# A7_MGT.net
KiCad netlist of a schematic drawn in Altium Designer
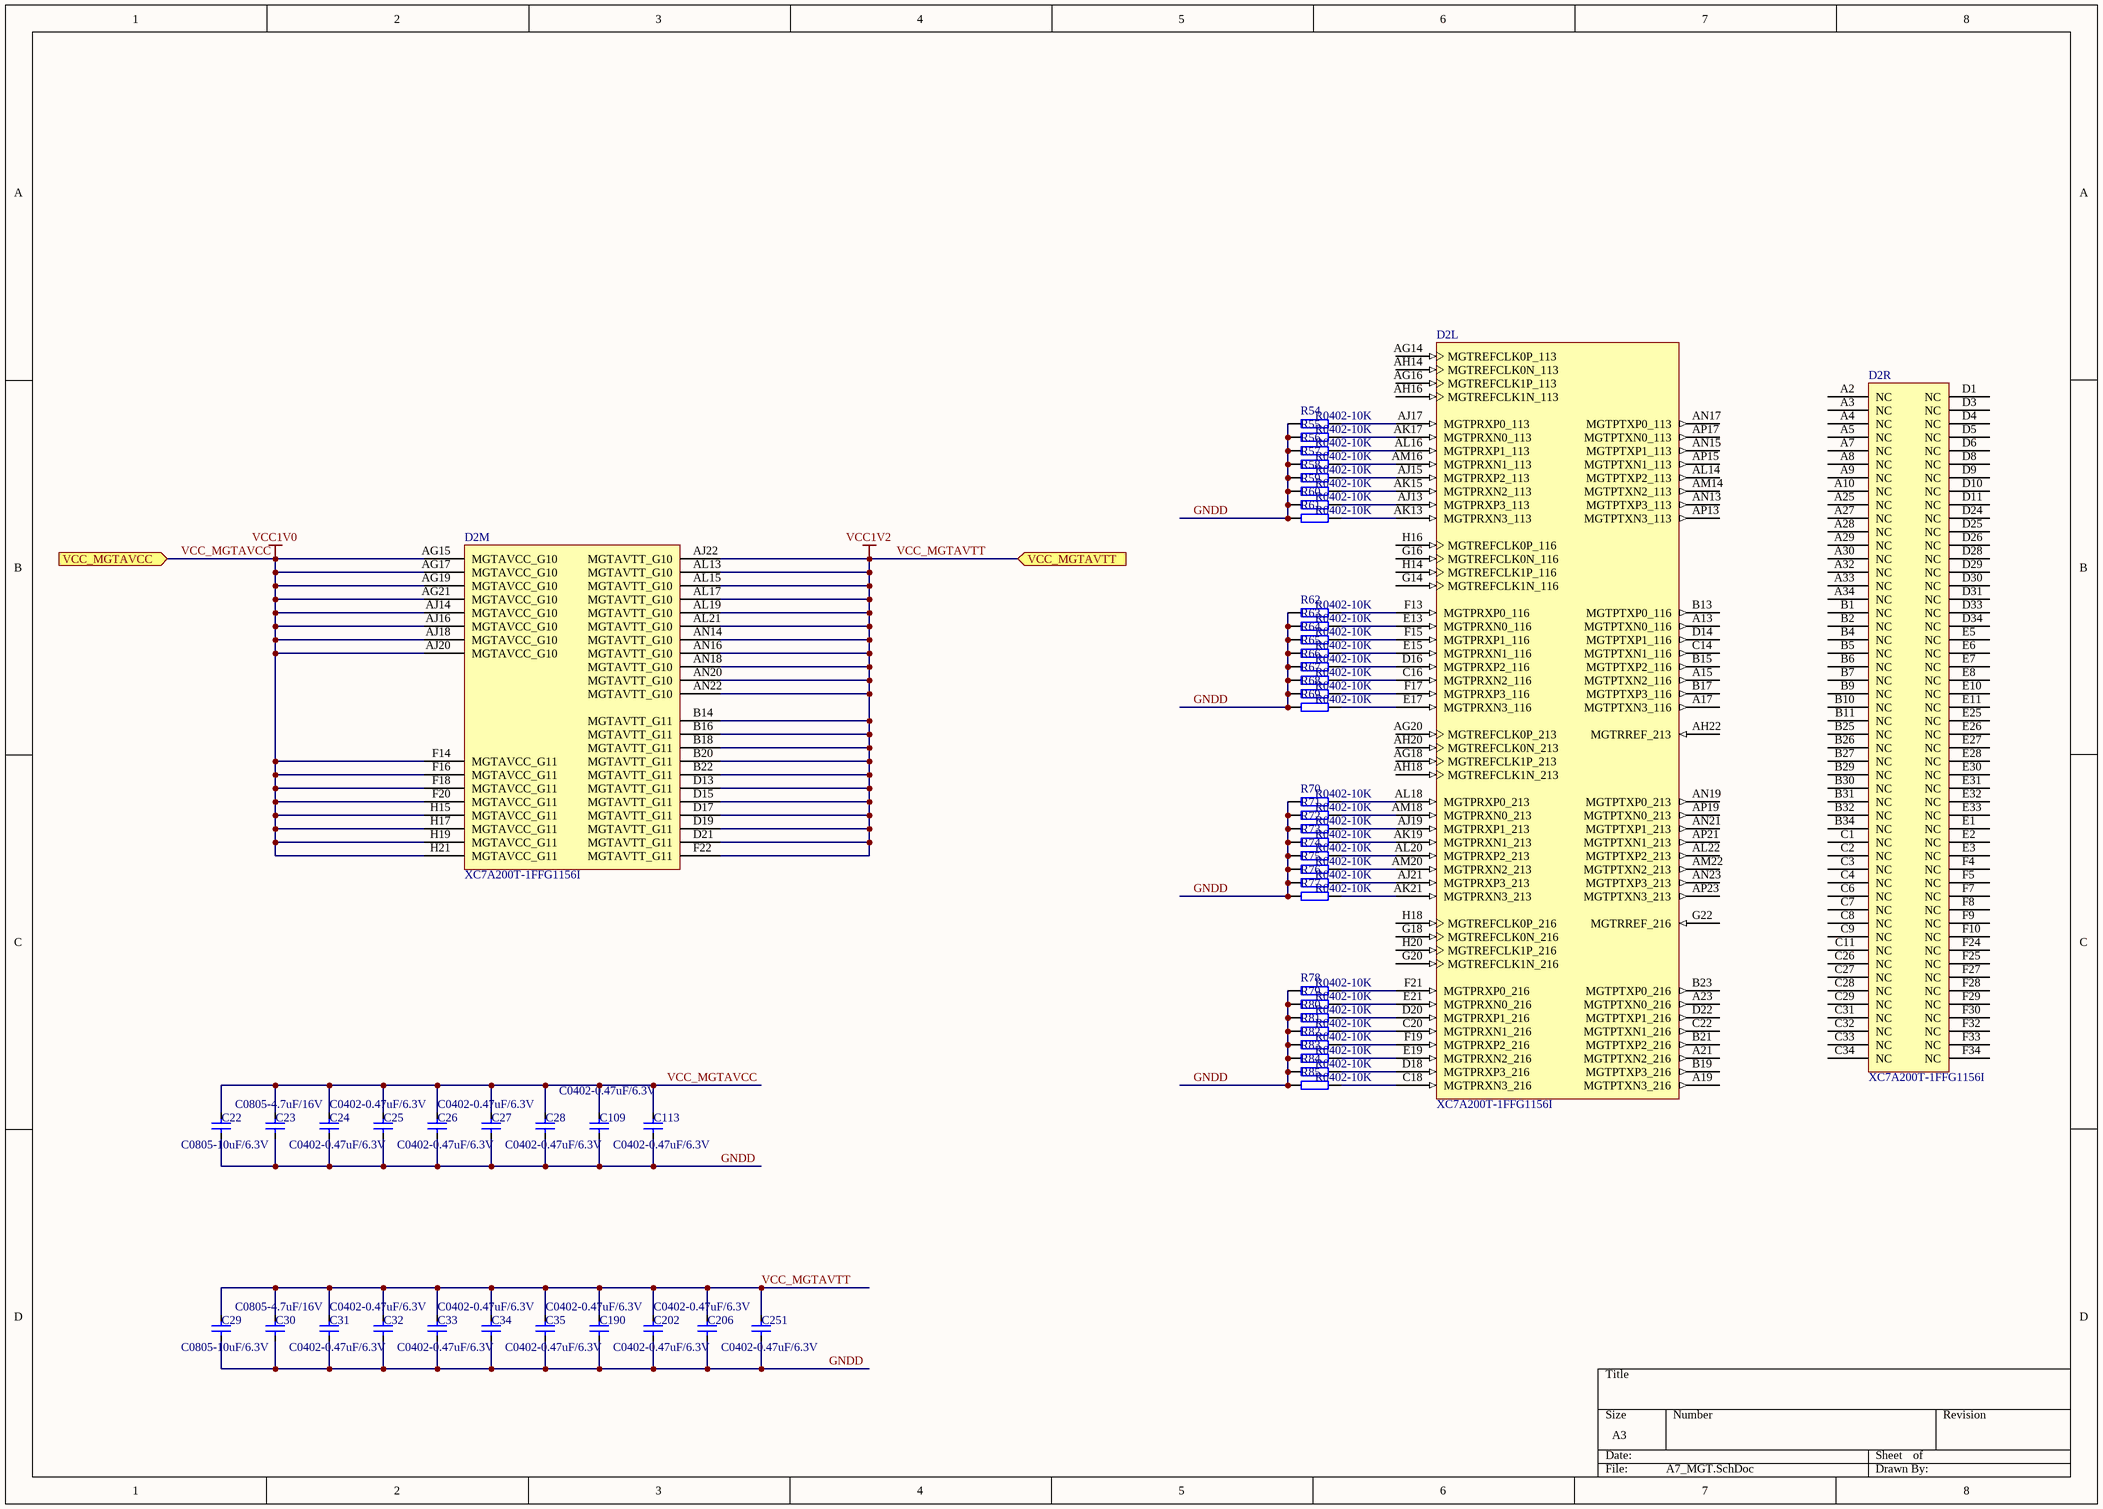
[diagram p0: A7_MGT.SchDoc]

(export (version "E")
  (design (tool "Eeschema 10.0.6"))
  (components
    (comp (ref "C22")
      (value "C0805-10uF/6.3V")
      (footprint "C0805")
      (fields (field (name "SCHEMATIC_PART") "CAP"))
      (libsource (lib "Database_Libs1") (part "CAP"))
    )
    (comp (ref "C23")
      (value "C0805-4.7uF/16V")
      (footprint "C0805")
      (description "X7R")
      (fields (field (name "SCHEMATIC_PART") "CAP") (field (name "MANUFACTURER") "SAMSUNG"))
      (libsource (lib "Database_Libs1") (part "CAP"))
    )
    (comp (ref "C24")
      (value "C0402-0.47uF/6.3V")
      (footprint "C0402")
      (description "X7R")
      (fields (field (name "SCHEMATIC_PART") "CAP") (field (name "MANUFACTURER") "SAMSUNG"))
      (libsource (lib "Database_Libs1") (part "CAP"))
    )
    (comp (ref "C25")
      (value "C0402-0.47uF/6.3V")
      (footprint "C0402")
      (description "X7R")
      (fields (field (name "SCHEMATIC_PART") "CAP") (field (name "MANUFACTURER") "SAMSUNG"))
      (libsource (lib "Database_Libs1") (part "CAP"))
    )
    (comp (ref "C26")
      (value "C0402-0.47uF/6.3V")
      (footprint "C0402")
      (description "X7R")
      (fields (field (name "SCHEMATIC_PART") "CAP") (field (name "MANUFACTURER") "SAMSUNG"))
      (libsource (lib "Database_Libs1") (part "CAP"))
    )
    (comp (ref "C27")
      (value "C0402-0.47uF/6.3V")
      (footprint "C0402")
      (description "X7R")
      (fields (field (name "SCHEMATIC_PART") "CAP") (field (name "MANUFACTURER") "SAMSUNG"))
      (libsource (lib "Database_Libs1") (part "CAP"))
    )
    (comp (ref "C28")
      (value "C0402-0.47uF/6.3V")
      (footprint "C0402")
      (description "X7R")
      (fields (field (name "SCHEMATIC_PART") "CAP") (field (name "MANUFACTURER") "SAMSUNG"))
      (libsource (lib "Database_Libs1") (part "CAP"))
    )
    (comp (ref "C29")
      (value "C0805-10uF/6.3V")
      (footprint "C0805")
      (fields (field (name "SCHEMATIC_PART") "CAP"))
      (libsource (lib "Database_Libs1") (part "CAP"))
    )
    (comp (ref "C30")
      (value "C0805-4.7uF/16V")
      (footprint "C0805")
      (description "X7R")
      (fields (field (name "SCHEMATIC_PART") "CAP") (field (name "MANUFACTURER") "SAMSUNG"))
      (libsource (lib "Database_Libs1") (part "CAP"))
    )
    (comp (ref "C31")
      (value "C0402-0.47uF/6.3V")
      (footprint "C0402")
      (description "X7R")
      (fields (field (name "SCHEMATIC_PART") "CAP") (field (name "MANUFACTURER") "SAMSUNG"))
      (libsource (lib "Database_Libs1") (part "CAP"))
    )
    (comp (ref "C32")
      (value "C0402-0.47uF/6.3V")
      (footprint "C0402")
      (description "X7R")
      (fields (field (name "SCHEMATIC_PART") "CAP") (field (name "MANUFACTURER") "SAMSUNG"))
      (libsource (lib "Database_Libs1") (part "CAP"))
    )
    (comp (ref "C33")
      (value "C0402-0.47uF/6.3V")
      (footprint "C0402")
      (description "X7R")
      (fields (field (name "SCHEMATIC_PART") "CAP") (field (name "MANUFACTURER") "SAMSUNG"))
      (libsource (lib "Database_Libs1") (part "CAP"))
    )
    (comp (ref "C34")
      (value "C0402-0.47uF/6.3V")
      (footprint "C0402")
      (description "X7R")
      (fields (field (name "SCHEMATIC_PART") "CAP") (field (name "MANUFACTURER") "SAMSUNG"))
      (libsource (lib "Database_Libs1") (part "CAP"))
    )
    (comp (ref "C35")
      (value "C0402-0.47uF/6.3V")
      (footprint "C0402")
      (description "X7R")
      (fields (field (name "SCHEMATIC_PART") "CAP") (field (name "MANUFACTURER") "SAMSUNG"))
      (libsource (lib "Database_Libs1") (part "CAP"))
    )
    (comp (ref "C109")
      (value "C0402-0.47uF/6.3V")
      (footprint "C0402")
      (description "X7R")
      (fields (field (name "SCHEMATIC_PART") "CAP") (field (name "MANUFACTURER") "SAMSUNG"))
      (libsource (lib "Database_Libs1") (part "CAP"))
    )
    (comp (ref "C113")
      (value "C0402-0.47uF/6.3V")
      (footprint "C0402")
      (description "X7R")
      (fields (field (name "SCHEMATIC_PART") "CAP") (field (name "MANUFACTURER") "SAMSUNG"))
      (libsource (lib "Database_Libs1") (part "CAP"))
    )
    (comp (ref "C190")
      (value "C0402-0.47uF/6.3V")
      (footprint "C0402")
      (description "X7R")
      (fields (field (name "SCHEMATIC_PART") "CAP") (field (name "MANUFACTURER") "SAMSUNG"))
      (libsource (lib "Database_Libs1") (part "CAP"))
    )
    (comp (ref "C202")
      (value "C0402-0.47uF/6.3V")
      (footprint "C0402")
      (description "X7R")
      (fields (field (name "SCHEMATIC_PART") "CAP") (field (name "MANUFACTURER") "SAMSUNG"))
      (libsource (lib "Database_Libs1") (part "CAP"))
    )
    (comp (ref "C206")
      (value "C0402-0.47uF/6.3V")
      (footprint "C0402")
      (description "X7R")
      (fields (field (name "SCHEMATIC_PART") "CAP") (field (name "MANUFACTURER") "SAMSUNG"))
      (libsource (lib "Database_Libs1") (part "CAP"))
    )
    (comp (ref "C251")
      (value "C0402-0.47uF/6.3V")
      (footprint "C0402")
      (description "X7R")
      (fields (field (name "SCHEMATIC_PART") "CAP") (field (name "MANUFACTURER") "SAMSUNG"))
      (libsource (lib "Database_Libs1") (part "CAP"))
    )
    (comp (ref "D2")
      (value "XC7A200T-1FFG1156I")
      (footprint "FFG1156")
      (description "Artix-7 FPGA, 500 User I/Os, 16 GTP, 1156-Ball BGA, Speed Grade 1, Industrial Grade, Pb-Free")
      (fields (field (name "GENERIC PART NUMBER") "XC7A200T") (field (name "MANUFACTURER") "Xilinx"))
      (libsource (lib "Xilinx Artix-7") (part "XC7A200T-1FFG1156I"))
    )
    (comp (ref "R54")
      (value "R0402-10K")
      (footprint "R0402")
      (fields (field (name "SCHEMATIC_PART") "RES") (field (name "MANUFACTURER") "SAMSUNG"))
      (libsource (lib "Database_Libs1") (part "RES"))
    )
    (comp (ref "R55")
      (value "R0402-10K")
      (footprint "R0402")
      (fields (field (name "SCHEMATIC_PART") "RES") (field (name "MANUFACTURER") "SAMSUNG"))
      (libsource (lib "Database_Libs1") (part "RES"))
    )
    (comp (ref "R56")
      (value "R0402-10K")
      (footprint "R0402")
      (fields (field (name "SCHEMATIC_PART") "RES") (field (name "MANUFACTURER") "SAMSUNG"))
      (libsource (lib "Database_Libs1") (part "RES"))
    )
    (comp (ref "R57")
      (value "R0402-10K")
      (footprint "R0402")
      (fields (field (name "SCHEMATIC_PART") "RES") (field (name "MANUFACTURER") "SAMSUNG"))
      (libsource (lib "Database_Libs1") (part "RES"))
    )
    (comp (ref "R58")
      (value "R0402-10K")
      (footprint "R0402")
      (fields (field (name "SCHEMATIC_PART") "RES") (field (name "MANUFACTURER") "SAMSUNG"))
      (libsource (lib "Database_Libs1") (part "RES"))
    )
    (comp (ref "R59")
      (value "R0402-10K")
      (footprint "R0402")
      (fields (field (name "SCHEMATIC_PART") "RES") (field (name "MANUFACTURER") "SAMSUNG"))
      (libsource (lib "Database_Libs1") (part "RES"))
    )
    (comp (ref "R60")
      (value "R0402-10K")
      (footprint "R0402")
      (fields (field (name "SCHEMATIC_PART") "RES") (field (name "MANUFACTURER") "SAMSUNG"))
      (libsource (lib "Database_Libs1") (part "RES"))
    )
    (comp (ref "R61")
      (value "R0402-10K")
      (footprint "R0402")
      (fields (field (name "SCHEMATIC_PART") "RES") (field (name "MANUFACTURER") "SAMSUNG"))
      (libsource (lib "Database_Libs1") (part "RES"))
    )
    (comp (ref "R62")
      (value "R0402-10K")
      (footprint "R0402")
      (fields (field (name "SCHEMATIC_PART") "RES") (field (name "MANUFACTURER") "SAMSUNG"))
      (libsource (lib "Database_Libs1") (part "RES"))
    )
    (comp (ref "R63")
      (value "R0402-10K")
      (footprint "R0402")
      (fields (field (name "SCHEMATIC_PART") "RES") (field (name "MANUFACTURER") "SAMSUNG"))
      (libsource (lib "Database_Libs1") (part "RES"))
    )
    (comp (ref "R64")
      (value "R0402-10K")
      (footprint "R0402")
      (fields (field (name "SCHEMATIC_PART") "RES") (field (name "MANUFACTURER") "SAMSUNG"))
      (libsource (lib "Database_Libs1") (part "RES"))
    )
    (comp (ref "R65")
      (value "R0402-10K")
      (footprint "R0402")
      (fields (field (name "SCHEMATIC_PART") "RES") (field (name "MANUFACTURER") "SAMSUNG"))
      (libsource (lib "Database_Libs1") (part "RES"))
    )
    (comp (ref "R66")
      (value "R0402-10K")
      (footprint "R0402")
      (fields (field (name "SCHEMATIC_PART") "RES") (field (name "MANUFACTURER") "SAMSUNG"))
      (libsource (lib "Database_Libs1") (part "RES"))
    )
    (comp (ref "R67")
      (value "R0402-10K")
      (footprint "R0402")
      (fields (field (name "SCHEMATIC_PART") "RES") (field (name "MANUFACTURER") "SAMSUNG"))
      (libsource (lib "Database_Libs1") (part "RES"))
    )
    (comp (ref "R68")
      (value "R0402-10K")
      (footprint "R0402")
      (fields (field (name "SCHEMATIC_PART") "RES") (field (name "MANUFACTURER") "SAMSUNG"))
      (libsource (lib "Database_Libs1") (part "RES"))
    )
    (comp (ref "R69")
      (value "R0402-10K")
      (footprint "R0402")
      (fields (field (name "SCHEMATIC_PART") "RES") (field (name "MANUFACTURER") "SAMSUNG"))
      (libsource (lib "Database_Libs1") (part "RES"))
    )
    (comp (ref "R70")
      (value "R0402-10K")
      (footprint "R0402")
      (fields (field (name "SCHEMATIC_PART") "RES") (field (name "MANUFACTURER") "SAMSUNG"))
      (libsource (lib "Database_Libs1") (part "RES"))
    )
    (comp (ref "R71")
      (value "R0402-10K")
      (footprint "R0402")
      (fields (field (name "SCHEMATIC_PART") "RES") (field (name "MANUFACTURER") "SAMSUNG"))
      (libsource (lib "Database_Libs1") (part "RES"))
    )
    (comp (ref "R72")
      (value "R0402-10K")
      (footprint "R0402")
      (fields (field (name "SCHEMATIC_PART") "RES") (field (name "MANUFACTURER") "SAMSUNG"))
      (libsource (lib "Database_Libs1") (part "RES"))
    )
    (comp (ref "R73")
      (value "R0402-10K")
      (footprint "R0402")
      (fields (field (name "SCHEMATIC_PART") "RES") (field (name "MANUFACTURER") "SAMSUNG"))
      (libsource (lib "Database_Libs1") (part "RES"))
    )
    (comp (ref "R74")
      (value "R0402-10K")
      (footprint "R0402")
      (fields (field (name "SCHEMATIC_PART") "RES") (field (name "MANUFACTURER") "SAMSUNG"))
      (libsource (lib "Database_Libs1") (part "RES"))
    )
    (comp (ref "R75")
      (value "R0402-10K")
      (footprint "R0402")
      (fields (field (name "SCHEMATIC_PART") "RES") (field (name "MANUFACTURER") "SAMSUNG"))
      (libsource (lib "Database_Libs1") (part "RES"))
    )
    (comp (ref "R76")
      (value "R0402-10K")
      (footprint "R0402")
      (fields (field (name "SCHEMATIC_PART") "RES") (field (name "MANUFACTURER") "SAMSUNG"))
      (libsource (lib "Database_Libs1") (part "RES"))
    )
    (comp (ref "R77")
      (value "R0402-10K")
      (footprint "R0402")
      (fields (field (name "SCHEMATIC_PART") "RES") (field (name "MANUFACTURER") "SAMSUNG"))
      (libsource (lib "Database_Libs1") (part "RES"))
    )
    (comp (ref "R78")
      (value "R0402-10K")
      (footprint "R0402")
      (fields (field (name "SCHEMATIC_PART") "RES") (field (name "MANUFACTURER") "SAMSUNG"))
      (libsource (lib "Database_Libs1") (part "RES"))
    )
    (comp (ref "R79")
      (value "R0402-10K")
      (footprint "R0402")
      (fields (field (name "SCHEMATIC_PART") "RES") (field (name "MANUFACTURER") "SAMSUNG"))
      (libsource (lib "Database_Libs1") (part "RES"))
    )
    (comp (ref "R80")
      (value "R0402-10K")
      (footprint "R0402")
      (fields (field (name "SCHEMATIC_PART") "RES") (field (name "MANUFACTURER") "SAMSUNG"))
      (libsource (lib "Database_Libs1") (part "RES"))
    )
    (comp (ref "R81")
      (value "R0402-10K")
      (footprint "R0402")
      (fields (field (name "SCHEMATIC_PART") "RES") (field (name "MANUFACTURER") "SAMSUNG"))
      (libsource (lib "Database_Libs1") (part "RES"))
    )
    (comp (ref "R82")
      (value "R0402-10K")
      (footprint "R0402")
      (fields (field (name "SCHEMATIC_PART") "RES") (field (name "MANUFACTURER") "SAMSUNG"))
      (libsource (lib "Database_Libs1") (part "RES"))
    )
    (comp (ref "R83")
      (value "R0402-10K")
      (footprint "R0402")
      (fields (field (name "SCHEMATIC_PART") "RES") (field (name "MANUFACTURER") "SAMSUNG"))
      (libsource (lib "Database_Libs1") (part "RES"))
    )
    (comp (ref "R84")
      (value "R0402-10K")
      (footprint "R0402")
      (fields (field (name "SCHEMATIC_PART") "RES") (field (name "MANUFACTURER") "SAMSUNG"))
      (libsource (lib "Database_Libs1") (part "RES"))
    )
    (comp (ref "R85")
      (value "R0402-10K")
      (footprint "R0402")
      (fields (field (name "SCHEMATIC_PART") "RES") (field (name "MANUFACTURER") "SAMSUNG"))
      (libsource (lib "Database_Libs1") (part "RES"))
    )
  )
  (nets
    (net (code "1") (name "/GNDD") (class "Default")
      (node (ref "C109") (pin "2") (pinfunction "2_2") (pintype "passive"))
      (node (ref "C113") (pin "2") (pinfunction "2_2") (pintype "passive"))
      (node (ref "C190") (pin "2") (pinfunction "2_2") (pintype "passive"))
      (node (ref "C202") (pin "2") (pinfunction "2_2") (pintype "passive"))
      (node (ref "C206") (pin "2") (pinfunction "2_2") (pintype "passive"))
      (node (ref "C22") (pin "2") (pinfunction "2_2") (pintype "passive"))
      (node (ref "C23") (pin "2") (pinfunction "2_2") (pintype "passive"))
      (node (ref "C24") (pin "2") (pinfunction "2_2") (pintype "passive"))
      (node (ref "C25") (pin "2") (pinfunction "2_2") (pintype "passive"))
      (node (ref "C251") (pin "2") (pinfunction "2_2") (pintype "passive"))
      (node (ref "C26") (pin "2") (pinfunction "2_2") (pintype "passive"))
      (node (ref "C27") (pin "2") (pinfunction "2_2") (pintype "passive"))
      (node (ref "C28") (pin "2") (pinfunction "2_2") (pintype "passive"))
      (node (ref "C29") (pin "2") (pinfunction "2_2") (pintype "passive"))
      (node (ref "C30") (pin "2") (pinfunction "2_2") (pintype "passive"))
      (node (ref "C31") (pin "2") (pinfunction "2_2") (pintype "passive"))
      (node (ref "C32") (pin "2") (pinfunction "2_2") (pintype "passive"))
      (node (ref "C33") (pin "2") (pinfunction "2_2") (pintype "passive"))
      (node (ref "C34") (pin "2") (pinfunction "2_2") (pintype "passive"))
      (node (ref "C35") (pin "2") (pinfunction "2_2") (pintype "passive"))
      (node (ref "R54") (pin "1") (pintype "passive"))
      (node (ref "R55") (pin "1") (pintype "passive"))
      (node (ref "R56") (pin "1") (pintype "passive"))
      (node (ref "R57") (pin "1") (pintype "passive"))
      (node (ref "R58") (pin "1") (pintype "passive"))
      (node (ref "R59") (pin "1") (pintype "passive"))
      (node (ref "R60") (pin "1") (pintype "passive"))
      (node (ref "R61") (pin "1") (pintype "passive"))
      (node (ref "R62") (pin "1") (pintype "passive"))
      (node (ref "R63") (pin "1") (pintype "passive"))
      (node (ref "R64") (pin "1") (pintype "passive"))
      (node (ref "R65") (pin "1") (pintype "passive"))
      (node (ref "R66") (pin "1") (pintype "passive"))
      (node (ref "R67") (pin "1") (pintype "passive"))
      (node (ref "R68") (pin "1") (pintype "passive"))
      (node (ref "R69") (pin "1") (pintype "passive"))
      (node (ref "R70") (pin "1") (pintype "passive"))
      (node (ref "R71") (pin "1") (pintype "passive"))
      (node (ref "R72") (pin "1") (pintype "passive"))
      (node (ref "R73") (pin "1") (pintype "passive"))
      (node (ref "R74") (pin "1") (pintype "passive"))
      (node (ref "R75") (pin "1") (pintype "passive"))
      (node (ref "R76") (pin "1") (pintype "passive"))
      (node (ref "R77") (pin "1") (pintype "passive"))
      (node (ref "R78") (pin "1") (pintype "passive"))
      (node (ref "R79") (pin "1") (pintype "passive"))
      (node (ref "R80") (pin "1") (pintype "passive"))
      (node (ref "R81") (pin "1") (pintype "passive"))
      (node (ref "R82") (pin "1") (pintype "passive"))
      (node (ref "R83") (pin "1") (pintype "passive"))
      (node (ref "R84") (pin "1") (pintype "passive"))
      (node (ref "R85") (pin "1") (pintype "passive"))
    )
    (net (code "2") (name "Net-(D2L-MGTPRXN0_113)") (class "Default")
      (node (ref "D2") (pin "AK17") (pinfunction "MGTPRXN0_113_AK17") (pintype "input"))
      (node (ref "R55") (pin "2") (pintype "passive"))
    )
    (net (code "3") (name "Net-(D2L-MGTPRXN0_116)") (class "Default")
      (node (ref "D2") (pin "E13") (pinfunction "MGTPRXN0_116_E13") (pintype "input"))
      (node (ref "R63") (pin "2") (pintype "passive"))
    )
    (net (code "4") (name "Net-(D2L-MGTPRXN0_213)") (class "Default")
      (node (ref "D2") (pin "AM18") (pinfunction "MGTPRXN0_213_AM18") (pintype "input"))
      (node (ref "R71") (pin "2") (pintype "passive"))
    )
    (net (code "5") (name "Net-(D2L-MGTPRXN0_216)") (class "Default")
      (node (ref "D2") (pin "E21") (pinfunction "MGTPRXN0_216_E21") (pintype "input"))
      (node (ref "R79") (pin "2") (pintype "passive"))
    )
    (net (code "6") (name "Net-(D2L-MGTPRXN1_113)") (class "Default")
      (node (ref "D2") (pin "AM16") (pinfunction "MGTPRXN1_113_AM16") (pintype "input"))
      (node (ref "R57") (pin "2") (pintype "passive"))
    )
    (net (code "7") (name "Net-(D2L-MGTPRXN1_116)") (class "Default")
      (node (ref "D2") (pin "E15") (pinfunction "MGTPRXN1_116_E15") (pintype "input"))
      (node (ref "R65") (pin "2") (pintype "passive"))
    )
    (net (code "8") (name "Net-(D2L-MGTPRXN1_213)") (class "Default")
      (node (ref "D2") (pin "AK19") (pinfunction "MGTPRXN1_213_AK19") (pintype "input"))
      (node (ref "R73") (pin "2") (pintype "passive"))
    )
    (net (code "9") (name "Net-(D2L-MGTPRXN1_216)") (class "Default")
      (node (ref "D2") (pin "C20") (pinfunction "MGTPRXN1_216_C20") (pintype "input"))
      (node (ref "R81") (pin "2") (pintype "passive"))
    )
    (net (code "10") (name "Net-(D2L-MGTPRXN2_113)") (class "Default")
      (node (ref "D2") (pin "AK15") (pinfunction "MGTPRXN2_113_AK15") (pintype "input"))
      (node (ref "R59") (pin "2") (pintype "passive"))
    )
    (net (code "11") (name "Net-(D2L-MGTPRXN2_116)") (class "Default")
      (node (ref "D2") (pin "C16") (pinfunction "MGTPRXN2_116_C16") (pintype "input"))
      (node (ref "R67") (pin "2") (pintype "passive"))
    )
    (net (code "12") (name "Net-(D2L-MGTPRXN2_213)") (class "Default")
      (node (ref "D2") (pin "AM20") (pinfunction "MGTPRXN2_213_AM20") (pintype "input"))
      (node (ref "R75") (pin "2") (pintype "passive"))
    )
    (net (code "13") (name "Net-(D2L-MGTPRXN2_216)") (class "Default")
      (node (ref "D2") (pin "E19") (pinfunction "MGTPRXN2_216_E19") (pintype "input"))
      (node (ref "R83") (pin "2") (pintype "passive"))
    )
    (net (code "14") (name "Net-(D2L-MGTPRXN3_113)") (class "Default")
      (node (ref "D2") (pin "AK13") (pinfunction "MGTPRXN3_113_AK13") (pintype "input"))
      (node (ref "R61") (pin "2") (pintype "passive"))
    )
    (net (code "15") (name "Net-(D2L-MGTPRXN3_116)") (class "Default")
      (node (ref "D2") (pin "E17") (pinfunction "MGTPRXN3_116_E17") (pintype "input"))
      (node (ref "R69") (pin "2") (pintype "passive"))
    )
    (net (code "16") (name "Net-(D2L-MGTPRXN3_213)") (class "Default")
      (node (ref "D2") (pin "AK21") (pinfunction "MGTPRXN3_213_AK21") (pintype "input"))
      (node (ref "R77") (pin "2") (pintype "passive"))
    )
    (net (code "17") (name "Net-(D2L-MGTPRXN3_216)") (class "Default")
      (node (ref "D2") (pin "C18") (pinfunction "MGTPRXN3_216_C18") (pintype "input"))
      (node (ref "R85") (pin "2") (pintype "passive"))
    )
    (net (code "18") (name "Net-(D2L-MGTPRXP0_113)") (class "Default")
      (node (ref "D2") (pin "AJ17") (pinfunction "MGTPRXP0_113_AJ17") (pintype "input"))
      (node (ref "R54") (pin "2") (pintype "passive"))
    )
    (net (code "19") (name "Net-(D2L-MGTPRXP0_116)") (class "Default")
      (node (ref "D2") (pin "F13") (pinfunction "MGTPRXP0_116_F13") (pintype "input"))
      (node (ref "R62") (pin "2") (pintype "passive"))
    )
    (net (code "20") (name "Net-(D2L-MGTPRXP0_213)") (class "Default")
      (node (ref "D2") (pin "AL18") (pinfunction "MGTPRXP0_213_AL18") (pintype "input"))
      (node (ref "R70") (pin "2") (pintype "passive"))
    )
    (net (code "21") (name "Net-(D2L-MGTPRXP0_216)") (class "Default")
      (node (ref "D2") (pin "F21") (pinfunction "MGTPRXP0_216_F21") (pintype "input"))
      (node (ref "R78") (pin "2") (pintype "passive"))
    )
    (net (code "22") (name "Net-(D2L-MGTPRXP1_113)") (class "Default")
      (node (ref "D2") (pin "AL16") (pinfunction "MGTPRXP1_113_AL16") (pintype "input"))
      (node (ref "R56") (pin "2") (pintype "passive"))
    )
    (net (code "23") (name "Net-(D2L-MGTPRXP1_116)") (class "Default")
      (node (ref "D2") (pin "F15") (pinfunction "MGTPRXP1_116_F15") (pintype "input"))
      (node (ref "R64") (pin "2") (pintype "passive"))
    )
    (net (code "24") (name "Net-(D2L-MGTPRXP1_213)") (class "Default")
      (node (ref "D2") (pin "AJ19") (pinfunction "MGTPRXP1_213_AJ19") (pintype "input"))
      (node (ref "R72") (pin "2") (pintype "passive"))
    )
    (net (code "25") (name "Net-(D2L-MGTPRXP1_216)") (class "Default")
      (node (ref "D2") (pin "D20") (pinfunction "MGTPRXP1_216_D20") (pintype "input"))
      (node (ref "R80") (pin "2") (pintype "passive"))
    )
    (net (code "26") (name "Net-(D2L-MGTPRXP2_113)") (class "Default")
      (node (ref "D2") (pin "AJ15") (pinfunction "MGTPRXP2_113_AJ15") (pintype "input"))
      (node (ref "R58") (pin "2") (pintype "passive"))
    )
    (net (code "27") (name "Net-(D2L-MGTPRXP2_116)") (class "Default")
      (node (ref "D2") (pin "D16") (pinfunction "MGTPRXP2_116_D16") (pintype "input"))
      (node (ref "R66") (pin "2") (pintype "passive"))
    )
    (net (code "28") (name "Net-(D2L-MGTPRXP2_213)") (class "Default")
      (node (ref "D2") (pin "AL20") (pinfunction "MGTPRXP2_213_AL20") (pintype "input"))
      (node (ref "R74") (pin "2") (pintype "passive"))
    )
    (net (code "29") (name "Net-(D2L-MGTPRXP2_216)") (class "Default")
      (node (ref "D2") (pin "F19") (pinfunction "MGTPRXP2_216_F19") (pintype "input"))
      (node (ref "R82") (pin "2") (pintype "passive"))
    )
    (net (code "30") (name "Net-(D2L-MGTPRXP3_113)") (class "Default")
      (node (ref "D2") (pin "AJ13") (pinfunction "MGTPRXP3_113_AJ13") (pintype "input"))
      (node (ref "R60") (pin "2") (pintype "passive"))
    )
    (net (code "31") (name "Net-(D2L-MGTPRXP3_116)") (class "Default")
      (node (ref "D2") (pin "F17") (pinfunction "MGTPRXP3_116_F17") (pintype "input"))
      (node (ref "R68") (pin "2") (pintype "passive"))
    )
    (net (code "32") (name "Net-(D2L-MGTPRXP3_213)") (class "Default")
      (node (ref "D2") (pin "AJ21") (pinfunction "MGTPRXP3_213_AJ21") (pintype "input"))
      (node (ref "R76") (pin "2") (pintype "passive"))
    )
    (net (code "33") (name "Net-(D2L-MGTPRXP3_216)") (class "Default")
      (node (ref "D2") (pin "D18") (pinfunction "MGTPRXP3_216_D18") (pintype "input"))
      (node (ref "R84") (pin "2") (pintype "passive"))
    )
    (net (code "34") (name "VCC1V0") (class "Default")
      (node (ref "C109") (pin "1") (pinfunction "1_1") (pintype "passive"))
      (node (ref "C113") (pin "1") (pinfunction "1_1") (pintype "passive"))
      (node (ref "C22") (pin "1") (pinfunction "1_1") (pintype "passive"))
      (node (ref "C23") (pin "1") (pinfunction "1_1") (pintype "passive"))
      (node (ref "C24") (pin "1") (pinfunction "1_1") (pintype "passive"))
      (node (ref "C25") (pin "1") (pinfunction "1_1") (pintype "passive"))
      (node (ref "C26") (pin "1") (pinfunction "1_1") (pintype "passive"))
      (node (ref "C27") (pin "1") (pinfunction "1_1") (pintype "passive"))
      (node (ref "C28") (pin "1") (pinfunction "1_1") (pintype "passive"))
      (node (ref "D2") (pin "AG15") (pinfunction "MGTAVCC_G10_AG15") (pintype "power_in"))
      (node (ref "D2") (pin "AG17") (pinfunction "MGTAVCC_G10_AG17") (pintype "power_in"))
      (node (ref "D2") (pin "AG19") (pinfunction "MGTAVCC_G10_AG19") (pintype "power_in"))
      (node (ref "D2") (pin "AG21") (pinfunction "MGTAVCC_G10_AG21") (pintype "power_in"))
      (node (ref "D2") (pin "AJ14") (pinfunction "MGTAVCC_G10_AJ14") (pintype "power_in"))
      (node (ref "D2") (pin "AJ16") (pinfunction "MGTAVCC_G10_AJ16") (pintype "power_in"))
      (node (ref "D2") (pin "AJ18") (pinfunction "MGTAVCC_G10_AJ18") (pintype "power_in"))
      (node (ref "D2") (pin "AJ20") (pinfunction "MGTAVCC_G10_AJ20") (pintype "power_in"))
      (node (ref "D2") (pin "F14") (pinfunction "MGTAVCC_G11_F14") (pintype "power_in"))
      (node (ref "D2") (pin "F16") (pinfunction "MGTAVCC_G11_F16") (pintype "power_in"))
      (node (ref "D2") (pin "F18") (pinfunction "MGTAVCC_G11_F18") (pintype "power_in"))
      (node (ref "D2") (pin "F20") (pinfunction "MGTAVCC_G11_F20") (pintype "power_in"))
      (node (ref "D2") (pin "H15") (pinfunction "MGTAVCC_G11_H15") (pintype "power_in"))
      (node (ref "D2") (pin "H17") (pinfunction "MGTAVCC_G11_H17") (pintype "power_in"))
      (node (ref "D2") (pin "H19") (pinfunction "MGTAVCC_G11_H19") (pintype "power_in"))
      (node (ref "D2") (pin "H21") (pinfunction "MGTAVCC_G11_H21") (pintype "power_in"))
    )
    (net (code "35") (name "VCC1V2") (class "Default")
      (node (ref "C190") (pin "1") (pinfunction "1_1") (pintype "passive"))
      (node (ref "C202") (pin "1") (pinfunction "1_1") (pintype "passive"))
      (node (ref "C206") (pin "1") (pinfunction "1_1") (pintype "passive"))
      (node (ref "C251") (pin "1") (pinfunction "1_1") (pintype "passive"))
      (node (ref "C29") (pin "1") (pinfunction "1_1") (pintype "passive"))
      (node (ref "C30") (pin "1") (pinfunction "1_1") (pintype "passive"))
      (node (ref "C31") (pin "1") (pinfunction "1_1") (pintype "passive"))
      (node (ref "C32") (pin "1") (pinfunction "1_1") (pintype "passive"))
      (node (ref "C33") (pin "1") (pinfunction "1_1") (pintype "passive"))
      (node (ref "C34") (pin "1") (pinfunction "1_1") (pintype "passive"))
      (node (ref "C35") (pin "1") (pinfunction "1_1") (pintype "passive"))
      (node (ref "D2") (pin "AJ22") (pinfunction "MGTAVTT_G10_AJ22") (pintype "power_in"))
      (node (ref "D2") (pin "AL13") (pinfunction "MGTAVTT_G10_AL13") (pintype "power_in"))
      (node (ref "D2") (pin "AL15") (pinfunction "MGTAVTT_G10_AL15") (pintype "power_in"))
      (node (ref "D2") (pin "AL17") (pinfunction "MGTAVTT_G10_AL17") (pintype "power_in"))
      (node (ref "D2") (pin "AL19") (pinfunction "MGTAVTT_G10_AL19") (pintype "power_in"))
      (node (ref "D2") (pin "AL21") (pinfunction "MGTAVTT_G10_AL21") (pintype "power_in"))
      (node (ref "D2") (pin "AN14") (pinfunction "MGTAVTT_G10_AN14") (pintype "power_in"))
      (node (ref "D2") (pin "AN16") (pinfunction "MGTAVTT_G10_AN16") (pintype "power_in"))
      (node (ref "D2") (pin "AN18") (pinfunction "MGTAVTT_G10_AN18") (pintype "power_in"))
      (node (ref "D2") (pin "AN20") (pinfunction "MGTAVTT_G10_AN20") (pintype "power_in"))
      (node (ref "D2") (pin "AN22") (pinfunction "MGTAVTT_G10_AN22") (pintype "power_in"))
      (node (ref "D2") (pin "B14") (pinfunction "MGTAVTT_G11_B14") (pintype "power_in"))
      (node (ref "D2") (pin "B16") (pinfunction "MGTAVTT_G11_B16") (pintype "power_in"))
      (node (ref "D2") (pin "B18") (pinfunction "MGTAVTT_G11_B18") (pintype "power_in"))
      (node (ref "D2") (pin "B20") (pinfunction "MGTAVTT_G11_B20") (pintype "power_in"))
      (node (ref "D2") (pin "B22") (pinfunction "MGTAVTT_G11_B22") (pintype "power_in"))
      (node (ref "D2") (pin "D13") (pinfunction "MGTAVTT_G11_D13") (pintype "power_in"))
      (node (ref "D2") (pin "D15") (pinfunction "MGTAVTT_G11_D15") (pintype "power_in"))
      (node (ref "D2") (pin "D17") (pinfunction "MGTAVTT_G11_D17") (pintype "power_in"))
      (node (ref "D2") (pin "D19") (pinfunction "MGTAVTT_G11_D19") (pintype "power_in"))
      (node (ref "D2") (pin "D21") (pinfunction "MGTAVTT_G11_D21") (pintype "power_in"))
      (node (ref "D2") (pin "F22") (pinfunction "MGTAVTT_G11_F22") (pintype "power_in"))
    )
    (net (code "36") (name "unconnected-(D2L-MGTPTXN0_113-PadAP17)") (class "Default")
      (node (ref "D2") (pin "AP17") (pinfunction "MGTPTXN0_113_AP17") (pintype "output"))
    )
    (net (code "37") (name "unconnected-(D2L-MGTPTXN0_116-PadA13)") (class "Default")
      (node (ref "D2") (pin "A13") (pinfunction "MGTPTXN0_116_A13") (pintype "output"))
    )
    (net (code "38") (name "unconnected-(D2L-MGTPTXN0_213-PadAP19)") (class "Default")
      (node (ref "D2") (pin "AP19") (pinfunction "MGTPTXN0_213_AP19") (pintype "output"))
    )
    (net (code "39") (name "unconnected-(D2L-MGTPTXN0_216-PadA23)") (class "Default")
      (node (ref "D2") (pin "A23") (pinfunction "MGTPTXN0_216_A23") (pintype "output"))
    )
    (net (code "40") (name "unconnected-(D2L-MGTPTXN1_113-PadAP15)") (class "Default")
      (node (ref "D2") (pin "AP15") (pinfunction "MGTPTXN1_113_AP15") (pintype "output"))
    )
    (net (code "41") (name "unconnected-(D2L-MGTPTXN1_116-PadC14)") (class "Default")
      (node (ref "D2") (pin "C14") (pinfunction "MGTPTXN1_116_C14") (pintype "output"))
    )
    (net (code "42") (name "unconnected-(D2L-MGTPTXN1_213-PadAP21)") (class "Default")
      (node (ref "D2") (pin "AP21") (pinfunction "MGTPTXN1_213_AP21") (pintype "output"))
    )
    (net (code "43") (name "unconnected-(D2L-MGTPTXN1_216-PadC22)") (class "Default")
      (node (ref "D2") (pin "C22") (pinfunction "MGTPTXN1_216_C22") (pintype "output"))
    )
    (net (code "44") (name "unconnected-(D2L-MGTPTXN2_113-PadAM14)") (class "Default")
      (node (ref "D2") (pin "AM14") (pinfunction "MGTPTXN2_113_AM14") (pintype "output"))
    )
    (net (code "45") (name "unconnected-(D2L-MGTPTXN2_116-PadA15)") (class "Default")
      (node (ref "D2") (pin "A15") (pinfunction "MGTPTXN2_116_A15") (pintype "output"))
    )
    (net (code "46") (name "unconnected-(D2L-MGTPTXN2_213-PadAM22)") (class "Default")
      (node (ref "D2") (pin "AM22") (pinfunction "MGTPTXN2_213_AM22") (pintype "output"))
    )
    (net (code "47") (name "unconnected-(D2L-MGTPTXN2_216-PadA21)") (class "Default")
      (node (ref "D2") (pin "A21") (pinfunction "MGTPTXN2_216_A21") (pintype "output"))
    )
    (net (code "48") (name "unconnected-(D2L-MGTPTXN3_113-PadAP13)") (class "Default")
      (node (ref "D2") (pin "AP13") (pinfunction "MGTPTXN3_113_AP13") (pintype "output"))
    )
    (net (code "49") (name "unconnected-(D2L-MGTPTXN3_116-PadA17)") (class "Default")
      (node (ref "D2") (pin "A17") (pinfunction "MGTPTXN3_116_A17") (pintype "output"))
    )
    (net (code "50") (name "unconnected-(D2L-MGTPTXN3_213-PadAP23)") (class "Default")
      (node (ref "D2") (pin "AP23") (pinfunction "MGTPTXN3_213_AP23") (pintype "output"))
    )
    (net (code "51") (name "unconnected-(D2L-MGTPTXN3_216-PadA19)") (class "Default")
      (node (ref "D2") (pin "A19") (pinfunction "MGTPTXN3_216_A19") (pintype "output"))
    )
    (net (code "52") (name "unconnected-(D2L-MGTPTXP0_113-PadAN17)") (class "Default")
      (node (ref "D2") (pin "AN17") (pinfunction "MGTPTXP0_113_AN17") (pintype "output"))
    )
    (net (code "53") (name "unconnected-(D2L-MGTPTXP0_116-PadB13)") (class "Default")
      (node (ref "D2") (pin "B13") (pinfunction "MGTPTXP0_116_B13") (pintype "output"))
    )
    (net (code "54") (name "unconnected-(D2L-MGTPTXP0_213-PadAN19)") (class "Default")
      (node (ref "D2") (pin "AN19") (pinfunction "MGTPTXP0_213_AN19") (pintype "output"))
    )
    (net (code "55") (name "unconnected-(D2L-MGTPTXP0_216-PadB23)") (class "Default")
      (node (ref "D2") (pin "B23") (pinfunction "MGTPTXP0_216_B23") (pintype "output"))
    )
    (net (code "56") (name "unconnected-(D2L-MGTPTXP1_113-PadAN15)") (class "Default")
      (node (ref "D2") (pin "AN15") (pinfunction "MGTPTXP1_113_AN15") (pintype "output"))
    )
    (net (code "57") (name "unconnected-(D2L-MGTPTXP1_116-PadD14)") (class "Default")
      (node (ref "D2") (pin "D14") (pinfunction "MGTPTXP1_116_D14") (pintype "output"))
    )
    (net (code "58") (name "unconnected-(D2L-MGTPTXP1_213-PadAN21)") (class "Default")
      (node (ref "D2") (pin "AN21") (pinfunction "MGTPTXP1_213_AN21") (pintype "output"))
    )
    (net (code "59") (name "unconnected-(D2L-MGTPTXP1_216-PadD22)") (class "Default")
      (node (ref "D2") (pin "D22") (pinfunction "MGTPTXP1_216_D22") (pintype "output"))
    )
    (net (code "60") (name "unconnected-(D2L-MGTPTXP2_113-PadAL14)") (class "Default")
      (node (ref "D2") (pin "AL14") (pinfunction "MGTPTXP2_113_AL14") (pintype "output"))
    )
    (net (code "61") (name "unconnected-(D2L-MGTPTXP2_116-PadB15)") (class "Default")
      (node (ref "D2") (pin "B15") (pinfunction "MGTPTXP2_116_B15") (pintype "output"))
    )
    (net (code "62") (name "unconnected-(D2L-MGTPTXP2_213-PadAL22)") (class "Default")
      (node (ref "D2") (pin "AL22") (pinfunction "MGTPTXP2_213_AL22") (pintype "output"))
    )
    (net (code "63") (name "unconnected-(D2L-MGTPTXP2_216-PadB21)") (class "Default")
      (node (ref "D2") (pin "B21") (pinfunction "MGTPTXP2_216_B21") (pintype "output"))
    )
    (net (code "64") (name "unconnected-(D2L-MGTPTXP3_113-PadAN13)") (class "Default")
      (node (ref "D2") (pin "AN13") (pinfunction "MGTPTXP3_113_AN13") (pintype "output"))
    )
    (net (code "65") (name "unconnected-(D2L-MGTPTXP3_116-PadB17)") (class "Default")
      (node (ref "D2") (pin "B17") (pinfunction "MGTPTXP3_116_B17") (pintype "output"))
    )
    (net (code "66") (name "unconnected-(D2L-MGTPTXP3_213-PadAN23)") (class "Default")
      (node (ref "D2") (pin "AN23") (pinfunction "MGTPTXP3_213_AN23") (pintype "output"))
    )
    (net (code "67") (name "unconnected-(D2L-MGTPTXP3_216-PadB19)") (class "Default")
      (node (ref "D2") (pin "B19") (pinfunction "MGTPTXP3_216_B19") (pintype "output"))
    )
    (net (code "68") (name "unconnected-(D2L-MGTREFCLK0N_113-PadAH14)") (class "Default")
      (node (ref "D2") (pin "AH14") (pinfunction "MGTREFCLK0N_113_AH14") (pintype "input"))
    )
    (net (code "69") (name "unconnected-(D2L-MGTREFCLK0N_116-PadG16)") (class "Default")
      (node (ref "D2") (pin "G16") (pinfunction "MGTREFCLK0N_116_G16") (pintype "input"))
    )
    (net (code "70") (name "unconnected-(D2L-MGTREFCLK0N_213-PadAH20)") (class "Default")
      (node (ref "D2") (pin "AH20") (pinfunction "MGTREFCLK0N_213_AH20") (pintype "input"))
    )
    (net (code "71") (name "unconnected-(D2L-MGTREFCLK0N_216-PadG18)") (class "Default")
      (node (ref "D2") (pin "G18") (pinfunction "MGTREFCLK0N_216_G18") (pintype "input"))
    )
    (net (code "72") (name "unconnected-(D2L-MGTREFCLK0P_113-PadAG14)") (class "Default")
      (node (ref "D2") (pin "AG14") (pinfunction "MGTREFCLK0P_113_AG14") (pintype "input"))
    )
    (net (code "73") (name "unconnected-(D2L-MGTREFCLK0P_116-PadH16)") (class "Default")
      (node (ref "D2") (pin "H16") (pinfunction "MGTREFCLK0P_116_H16") (pintype "input"))
    )
    (net (code "74") (name "unconnected-(D2L-MGTREFCLK0P_213-PadAG20)") (class "Default")
      (node (ref "D2") (pin "AG20") (pinfunction "MGTREFCLK0P_213_AG20") (pintype "input"))
    )
    (net (code "75") (name "unconnected-(D2L-MGTREFCLK0P_216-PadH18)") (class "Default")
      (node (ref "D2") (pin "H18") (pinfunction "MGTREFCLK0P_216_H18") (pintype "input"))
    )
    (net (code "76") (name "unconnected-(D2L-MGTREFCLK1N_113-PadAH16)") (class "Default")
      (node (ref "D2") (pin "AH16") (pinfunction "MGTREFCLK1N_113_AH16") (pintype "input"))
    )
    (net (code "77") (name "unconnected-(D2L-MGTREFCLK1N_116-PadG14)") (class "Default")
      (node (ref "D2") (pin "G14") (pinfunction "MGTREFCLK1N_116_G14") (pintype "input"))
    )
    (net (code "78") (name "unconnected-(D2L-MGTREFCLK1N_213-PadAH18)") (class "Default")
      (node (ref "D2") (pin "AH18") (pinfunction "MGTREFCLK1N_213_AH18") (pintype "input"))
    )
    (net (code "79") (name "unconnected-(D2L-MGTREFCLK1N_216-PadG20)") (class "Default")
      (node (ref "D2") (pin "G20") (pinfunction "MGTREFCLK1N_216_G20") (pintype "input"))
    )
    (net (code "80") (name "unconnected-(D2L-MGTREFCLK1P_113-PadAG16)") (class "Default")
      (node (ref "D2") (pin "AG16") (pinfunction "MGTREFCLK1P_113_AG16") (pintype "input"))
    )
    (net (code "81") (name "unconnected-(D2L-MGTREFCLK1P_116-PadH14)") (class "Default")
      (node (ref "D2") (pin "H14") (pinfunction "MGTREFCLK1P_116_H14") (pintype "input"))
    )
    (net (code "82") (name "unconnected-(D2L-MGTREFCLK1P_213-PadAG18)") (class "Default")
      (node (ref "D2") (pin "AG18") (pinfunction "MGTREFCLK1P_213_AG18") (pintype "input"))
    )
    (net (code "83") (name "unconnected-(D2L-MGTREFCLK1P_216-PadH20)") (class "Default")
      (node (ref "D2") (pin "H20") (pinfunction "MGTREFCLK1P_216_H20") (pintype "input"))
    )
    (net (code "84") (name "unconnected-(D2L-MGTRREF_213-PadAH22)") (class "Default")
      (node (ref "D2") (pin "AH22") (pinfunction "MGTRREF_213_AH22") (pintype "input"))
    )
    (net (code "85") (name "unconnected-(D2L-MGTRREF_216-PadG22)") (class "Default")
      (node (ref "D2") (pin "G22") (pinfunction "MGTRREF_216_G22") (pintype "input"))
    )
    (net (code "86") (name "unconnected-(D2R-NC-PadA2)") (class "Default")
      (node (ref "D2") (pin "A2") (pinfunction "NC_A2") (pintype "passive"))
    )
    (net (code "87") (name "unconnected-(D2R-NC-PadA3)") (class "Default")
      (node (ref "D2") (pin "A3") (pinfunction "NC_A3") (pintype "passive"))
    )
    (net (code "88") (name "unconnected-(D2R-NC-PadA4)") (class "Default")
      (node (ref "D2") (pin "A4") (pinfunction "NC_A4") (pintype "passive"))
    )
    (net (code "89") (name "unconnected-(D2R-NC-PadA5)") (class "Default")
      (node (ref "D2") (pin "A5") (pinfunction "NC_A5") (pintype "passive"))
    )
    (net (code "90") (name "unconnected-(D2R-NC-PadA7)") (class "Default")
      (node (ref "D2") (pin "A7") (pinfunction "NC_A7") (pintype "passive"))
    )
    (net (code "91") (name "unconnected-(D2R-NC-PadA8)") (class "Default")
      (node (ref "D2") (pin "A8") (pinfunction "NC_A8") (pintype "passive"))
    )
    (net (code "92") (name "unconnected-(D2R-NC-PadA9)") (class "Default")
      (node (ref "D2") (pin "A9") (pinfunction "NC_A9") (pintype "passive"))
    )
    (net (code "93") (name "unconnected-(D2R-NC-PadA10)") (class "Default")
      (node (ref "D2") (pin "A10") (pinfunction "NC_A10") (pintype "passive"))
    )
    (net (code "94") (name "unconnected-(D2R-NC-PadA25)") (class "Default")
      (node (ref "D2") (pin "A25") (pinfunction "NC_A25") (pintype "passive"))
    )
    (net (code "95") (name "unconnected-(D2R-NC-PadA27)") (class "Default")
      (node (ref "D2") (pin "A27") (pinfunction "NC_A27") (pintype "passive"))
    )
    (net (code "96") (name "unconnected-(D2R-NC-PadA28)") (class "Default")
      (node (ref "D2") (pin "A28") (pinfunction "NC_A28") (pintype "passive"))
    )
    (net (code "97") (name "unconnected-(D2R-NC-PadA29)") (class "Default")
      (node (ref "D2") (pin "A29") (pinfunction "NC_A29") (pintype "passive"))
    )
    (net (code "98") (name "unconnected-(D2R-NC-PadA30)") (class "Default")
      (node (ref "D2") (pin "A30") (pinfunction "NC_A30") (pintype "passive"))
    )
    (net (code "99") (name "unconnected-(D2R-NC-PadA32)") (class "Default")
      (node (ref "D2") (pin "A32") (pinfunction "NC_A32") (pintype "passive"))
    )
    (net (code "100") (name "unconnected-(D2R-NC-PadA33)") (class "Default")
      (node (ref "D2") (pin "A33") (pinfunction "NC_A33") (pintype "passive"))
    )
    (net (code "101") (name "unconnected-(D2R-NC-PadA34)") (class "Default")
      (node (ref "D2") (pin "A34") (pinfunction "NC_A34") (pintype "passive"))
    )
    (net (code "102") (name "unconnected-(D2R-NC-PadB1)") (class "Default")
      (node (ref "D2") (pin "B1") (pinfunction "NC_B1") (pintype "passive"))
    )
    (net (code "103") (name "unconnected-(D2R-NC-PadB2)") (class "Default")
      (node (ref "D2") (pin "B2") (pinfunction "NC_B2") (pintype "passive"))
    )
    (net (code "104") (name "unconnected-(D2R-NC-PadB4)") (class "Default")
      (node (ref "D2") (pin "B4") (pinfunction "NC_B4") (pintype "passive"))
    )
    (net (code "105") (name "unconnected-(D2R-NC-PadB5)") (class "Default")
      (node (ref "D2") (pin "B5") (pinfunction "NC_B5") (pintype "passive"))
    )
    (net (code "106") (name "unconnected-(D2R-NC-PadB6)") (class "Default")
      (node (ref "D2") (pin "B6") (pinfunction "NC_B6") (pintype "passive"))
    )
    (net (code "107") (name "unconnected-(D2R-NC-PadB7)") (class "Default")
      (node (ref "D2") (pin "B7") (pinfunction "NC_B7") (pintype "passive"))
    )
    (net (code "108") (name "unconnected-(D2R-NC-PadB9)") (class "Default")
      (node (ref "D2") (pin "B9") (pinfunction "NC_B9") (pintype "passive"))
    )
    (net (code "109") (name "unconnected-(D2R-NC-PadB10)") (class "Default")
      (node (ref "D2") (pin "B10") (pinfunction "NC_B10") (pintype "passive"))
    )
    (net (code "110") (name "unconnected-(D2R-NC-PadB11)") (class "Default")
      (node (ref "D2") (pin "B11") (pinfunction "NC_B11") (pintype "passive"))
    )
    (net (code "111") (name "unconnected-(D2R-NC-PadB25)") (class "Default")
      (node (ref "D2") (pin "B25") (pinfunction "NC_B25") (pintype "passive"))
    )
    (net (code "112") (name "unconnected-(D2R-NC-PadB26)") (class "Default")
      (node (ref "D2") (pin "B26") (pinfunction "NC_B26") (pintype "passive"))
    )
    (net (code "113") (name "unconnected-(D2R-NC-PadB27)") (class "Default")
      (node (ref "D2") (pin "B27") (pinfunction "NC_B27") (pintype "passive"))
    )
    (net (code "114") (name "unconnected-(D2R-NC-PadB29)") (class "Default")
      (node (ref "D2") (pin "B29") (pinfunction "NC_B29") (pintype "passive"))
    )
    (net (code "115") (name "unconnected-(D2R-NC-PadB30)") (class "Default")
      (node (ref "D2") (pin "B30") (pinfunction "NC_B30") (pintype "passive"))
    )
    (net (code "116") (name "unconnected-(D2R-NC-PadB31)") (class "Default")
      (node (ref "D2") (pin "B31") (pinfunction "NC_B31") (pintype "passive"))
    )
    (net (code "117") (name "unconnected-(D2R-NC-PadB32)") (class "Default")
      (node (ref "D2") (pin "B32") (pinfunction "NC_B32") (pintype "passive"))
    )
    (net (code "118") (name "unconnected-(D2R-NC-PadB34)") (class "Default")
      (node (ref "D2") (pin "B34") (pinfunction "NC_B34") (pintype "passive"))
    )
    (net (code "119") (name "unconnected-(D2R-NC-PadC1)") (class "Default")
      (node (ref "D2") (pin "C1") (pinfunction "NC_C1") (pintype "passive"))
    )
    (net (code "120") (name "unconnected-(D2R-NC-PadC2)") (class "Default")
      (node (ref "D2") (pin "C2") (pinfunction "NC_C2") (pintype "passive"))
    )
    (net (code "121") (name "unconnected-(D2R-NC-PadC3)") (class "Default")
      (node (ref "D2") (pin "C3") (pinfunction "NC_C3") (pintype "passive"))
    )
    (net (code "122") (name "unconnected-(D2R-NC-PadC4)") (class "Default")
      (node (ref "D2") (pin "C4") (pinfunction "NC_C4") (pintype "passive"))
    )
    (net (code "123") (name "unconnected-(D2R-NC-PadC6)") (class "Default")
      (node (ref "D2") (pin "C6") (pinfunction "NC_C6") (pintype "passive"))
    )
    (net (code "124") (name "unconnected-(D2R-NC-PadC7)") (class "Default")
      (node (ref "D2") (pin "C7") (pinfunction "NC_C7") (pintype "passive"))
    )
    (net (code "125") (name "unconnected-(D2R-NC-PadC8)") (class "Default")
      (node (ref "D2") (pin "C8") (pinfunction "NC_C8") (pintype "passive"))
    )
    (net (code "126") (name "unconnected-(D2R-NC-PadC9)") (class "Default")
      (node (ref "D2") (pin "C9") (pinfunction "NC_C9") (pintype "passive"))
    )
    (net (code "127") (name "unconnected-(D2R-NC-PadC11)") (class "Default")
      (node (ref "D2") (pin "C11") (pinfunction "NC_C11") (pintype "passive"))
    )
    (net (code "128") (name "unconnected-(D2R-NC-PadC26)") (class "Default")
      (node (ref "D2") (pin "C26") (pinfunction "NC_C26") (pintype "passive"))
    )
    (net (code "129") (name "unconnected-(D2R-NC-PadC27)") (class "Default")
      (node (ref "D2") (pin "C27") (pinfunction "NC_C27") (pintype "passive"))
    )
    (net (code "130") (name "unconnected-(D2R-NC-PadC28)") (class "Default")
      (node (ref "D2") (pin "C28") (pinfunction "NC_C28") (pintype "passive"))
    )
    (net (code "131") (name "unconnected-(D2R-NC-PadC29)") (class "Default")
      (node (ref "D2") (pin "C29") (pinfunction "NC_C29") (pintype "passive"))
    )
    (net (code "132") (name "unconnected-(D2R-NC-PadC31)") (class "Default")
      (node (ref "D2") (pin "C31") (pinfunction "NC_C31") (pintype "passive"))
    )
    (net (code "133") (name "unconnected-(D2R-NC-PadC32)") (class "Default")
      (node (ref "D2") (pin "C32") (pinfunction "NC_C32") (pintype "passive"))
    )
    (net (code "134") (name "unconnected-(D2R-NC-PadC33)") (class "Default")
      (node (ref "D2") (pin "C33") (pinfunction "NC_C33") (pintype "passive"))
    )
    (net (code "135") (name "unconnected-(D2R-NC-PadC34)") (class "Default")
      (node (ref "D2") (pin "C34") (pinfunction "NC_C34") (pintype "passive"))
    )
    (net (code "136") (name "unconnected-(D2R-NC-PadD1)") (class "Default")
      (node (ref "D2") (pin "D1") (pinfunction "NC_D1") (pintype "passive"))
    )
    (net (code "137") (name "unconnected-(D2R-NC-PadD3)") (class "Default")
      (node (ref "D2") (pin "D3") (pinfunction "NC_D3") (pintype "passive"))
    )
    (net (code "138") (name "unconnected-(D2R-NC-PadD4)") (class "Default")
      (node (ref "D2") (pin "D4") (pinfunction "NC_D4") (pintype "passive"))
    )
    (net (code "139") (name "unconnected-(D2R-NC-PadD5)") (class "Default")
      (node (ref "D2") (pin "D5") (pinfunction "NC_D5") (pintype "passive"))
    )
    (net (code "140") (name "unconnected-(D2R-NC-PadD6)") (class "Default")
      (node (ref "D2") (pin "D6") (pinfunction "NC_D6") (pintype "passive"))
    )
    (net (code "141") (name "unconnected-(D2R-NC-PadD8)") (class "Default")
      (node (ref "D2") (pin "D8") (pinfunction "NC_D8") (pintype "passive"))
    )
    (net (code "142") (name "unconnected-(D2R-NC-PadD9)") (class "Default")
      (node (ref "D2") (pin "D9") (pinfunction "NC_D9") (pintype "passive"))
    )
    (net (code "143") (name "unconnected-(D2R-NC-PadD10)") (class "Default")
      (node (ref "D2") (pin "D10") (pinfunction "NC_D10") (pintype "passive"))
    )
    (net (code "144") (name "unconnected-(D2R-NC-PadD11)") (class "Default")
      (node (ref "D2") (pin "D11") (pinfunction "NC_D11") (pintype "passive"))
    )
    (net (code "145") (name "unconnected-(D2R-NC-PadD24)") (class "Default")
      (node (ref "D2") (pin "D24") (pinfunction "NC_D24") (pintype "passive"))
    )
    (net (code "146") (name "unconnected-(D2R-NC-PadD25)") (class "Default")
      (node (ref "D2") (pin "D25") (pinfunction "NC_D25") (pintype "passive"))
    )
    (net (code "147") (name "unconnected-(D2R-NC-PadD26)") (class "Default")
      (node (ref "D2") (pin "D26") (pinfunction "NC_D26") (pintype "passive"))
    )
    (net (code "148") (name "unconnected-(D2R-NC-PadD28)") (class "Default")
      (node (ref "D2") (pin "D28") (pinfunction "NC_D28") (pintype "passive"))
    )
    (net (code "149") (name "unconnected-(D2R-NC-PadD29)") (class "Default")
      (node (ref "D2") (pin "D29") (pinfunction "NC_D29") (pintype "passive"))
    )
    (net (code "150") (name "unconnected-(D2R-NC-PadD30)") (class "Default")
      (node (ref "D2") (pin "D30") (pinfunction "NC_D30") (pintype "passive"))
    )
    (net (code "151") (name "unconnected-(D2R-NC-PadD31)") (class "Default")
      (node (ref "D2") (pin "D31") (pinfunction "NC_D31") (pintype "passive"))
    )
    (net (code "152") (name "unconnected-(D2R-NC-PadD33)") (class "Default")
      (node (ref "D2") (pin "D33") (pinfunction "NC_D33") (pintype "passive"))
    )
    (net (code "153") (name "unconnected-(D2R-NC-PadD34)") (class "Default")
      (node (ref "D2") (pin "D34") (pinfunction "NC_D34") (pintype "passive"))
    )
    (net (code "154") (name "unconnected-(D2R-NC-PadE1)") (class "Default")
      (node (ref "D2") (pin "E1") (pinfunction "NC_E1") (pintype "passive"))
    )
    (net (code "155") (name "unconnected-(D2R-NC-PadE2)") (class "Default")
      (node (ref "D2") (pin "E2") (pinfunction "NC_E2") (pintype "passive"))
    )
    (net (code "156") (name "unconnected-(D2R-NC-PadE3)") (class "Default")
      (node (ref "D2") (pin "E3") (pinfunction "NC_E3") (pintype "passive"))
    )
    (net (code "157") (name "unconnected-(D2R-NC-PadE5)") (class "Default")
      (node (ref "D2") (pin "E5") (pinfunction "NC_E5") (pintype "passive"))
    )
    (net (code "158") (name "unconnected-(D2R-NC-PadE6)") (class "Default")
      (node (ref "D2") (pin "E6") (pinfunction "NC_E6") (pintype "passive"))
    )
    (net (code "159") (name "unconnected-(D2R-NC-PadE7)") (class "Default")
      (node (ref "D2") (pin "E7") (pinfunction "NC_E7") (pintype "passive"))
    )
    (net (code "160") (name "unconnected-(D2R-NC-PadE8)") (class "Default")
      (node (ref "D2") (pin "E8") (pinfunction "NC_E8") (pintype "passive"))
    )
    (net (code "161") (name "unconnected-(D2R-NC-PadE10)") (class "Default")
      (node (ref "D2") (pin "E10") (pinfunction "NC_E10") (pintype "passive"))
    )
    (net (code "162") (name "unconnected-(D2R-NC-PadE11)") (class "Default")
      (node (ref "D2") (pin "E11") (pinfunction "NC_E11") (pintype "passive"))
    )
    (net (code "163") (name "unconnected-(D2R-NC-PadE25)") (class "Default")
      (node (ref "D2") (pin "E25") (pinfunction "NC_E25") (pintype "passive"))
    )
    (net (code "164") (name "unconnected-(D2R-NC-PadE26)") (class "Default")
      (node (ref "D2") (pin "E26") (pinfunction "NC_E26") (pintype "passive"))
    )
    (net (code "165") (name "unconnected-(D2R-NC-PadE27)") (class "Default")
      (node (ref "D2") (pin "E27") (pinfunction "NC_E27") (pintype "passive"))
    )
    (net (code "166") (name "unconnected-(D2R-NC-PadE28)") (class "Default")
      (node (ref "D2") (pin "E28") (pinfunction "NC_E28") (pintype "passive"))
    )
    (net (code "167") (name "unconnected-(D2R-NC-PadE30)") (class "Default")
      (node (ref "D2") (pin "E30") (pinfunction "NC_E30") (pintype "passive"))
    )
    (net (code "168") (name "unconnected-(D2R-NC-PadE31)") (class "Default")
      (node (ref "D2") (pin "E31") (pinfunction "NC_E31") (pintype "passive"))
    )
    (net (code "169") (name "unconnected-(D2R-NC-PadE32)") (class "Default")
      (node (ref "D2") (pin "E32") (pinfunction "NC_E32") (pintype "passive"))
    )
    (net (code "170") (name "unconnected-(D2R-NC-PadE33)") (class "Default")
      (node (ref "D2") (pin "E33") (pinfunction "NC_E33") (pintype "passive"))
    )
    (net (code "171") (name "unconnected-(D2R-NC-PadF4)") (class "Default")
      (node (ref "D2") (pin "F4") (pinfunction "NC_F4") (pintype "passive"))
    )
    (net (code "172") (name "unconnected-(D2R-NC-PadF5)") (class "Default")
      (node (ref "D2") (pin "F5") (pinfunction "NC_F5") (pintype "passive"))
    )
    (net (code "173") (name "unconnected-(D2R-NC-PadF7)") (class "Default")
      (node (ref "D2") (pin "F7") (pinfunction "NC_F7") (pintype "passive"))
    )
    (net (code "174") (name "unconnected-(D2R-NC-PadF8)") (class "Default")
      (node (ref "D2") (pin "F8") (pinfunction "NC_F8") (pintype "passive"))
    )
    (net (code "175") (name "unconnected-(D2R-NC-PadF9)") (class "Default")
      (node (ref "D2") (pin "F9") (pinfunction "NC_F9") (pintype "passive"))
    )
    (net (code "176") (name "unconnected-(D2R-NC-PadF10)") (class "Default")
      (node (ref "D2") (pin "F10") (pinfunction "NC_F10") (pintype "passive"))
    )
    (net (code "177") (name "unconnected-(D2R-NC-PadF24)") (class "Default")
      (node (ref "D2") (pin "F24") (pinfunction "NC_F24") (pintype "passive"))
    )
    (net (code "178") (name "unconnected-(D2R-NC-PadF25)") (class "Default")
      (node (ref "D2") (pin "F25") (pinfunction "NC_F25") (pintype "passive"))
    )
    (net (code "179") (name "unconnected-(D2R-NC-PadF27)") (class "Default")
      (node (ref "D2") (pin "F27") (pinfunction "NC_F27") (pintype "passive"))
    )
    (net (code "180") (name "unconnected-(D2R-NC-PadF28)") (class "Default")
      (node (ref "D2") (pin "F28") (pinfunction "NC_F28") (pintype "passive"))
    )
    (net (code "181") (name "unconnected-(D2R-NC-PadF29)") (class "Default")
      (node (ref "D2") (pin "F29") (pinfunction "NC_F29") (pintype "passive"))
    )
    (net (code "182") (name "unconnected-(D2R-NC-PadF30)") (class "Default")
      (node (ref "D2") (pin "F30") (pinfunction "NC_F30") (pintype "passive"))
    )
    (net (code "183") (name "unconnected-(D2R-NC-PadF32)") (class "Default")
      (node (ref "D2") (pin "F32") (pinfunction "NC_F32") (pintype "passive"))
    )
    (net (code "184") (name "unconnected-(D2R-NC-PadF33)") (class "Default")
      (node (ref "D2") (pin "F33") (pinfunction "NC_F33") (pintype "passive"))
    )
    (net (code "185") (name "unconnected-(D2R-NC-PadF34)") (class "Default")
      (node (ref "D2") (pin "F34") (pinfunction "NC_F34") (pintype "passive"))
    )
  )
)
